# ButtonHack.net
KiCad netlist of a schematic drawn in EAGLE
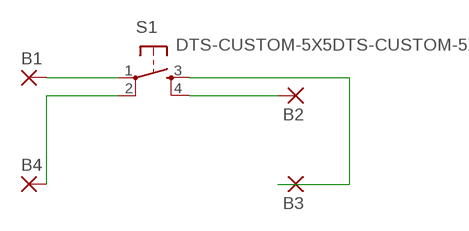
[diagram p0: schematic, sheet 1]

(export (version "E")
  (design (tool "Eeschema 10.0.6"))
  (components
    (comp (ref "B1")
      (value "2,54/0,8")
      (footprint "eagle-import:2,54_0,8")
      (libsource (lib "eagle-import") (part "2,54/0,8"))
    )
    (comp (ref "B2")
      (value "2,54/0,8")
      (footprint "eagle-import:2,54_0,8")
      (libsource (lib "eagle-import") (part "2,54/0,8"))
    )
    (comp (ref "B3")
      (value "2,54/0,8")
      (footprint "eagle-import:2,54_0,8")
      (libsource (lib "eagle-import") (part "2,54/0,8"))
    )
    (comp (ref "B4")
      (value "2,54/0,8")
      (footprint "eagle-import:2,54_0,8")
      (libsource (lib "eagle-import") (part "2,54/0,8"))
    )
    (comp (ref "S1")
      (value "DTS-CUSTOM-5X5DTS-CUSTOM-5X5")
      (footprint "eagle-import:DTS-CUSTOM-5X5")
      (libsource (lib "eagle-import") (part "DTS-CUSTOM-5X5DTS-CUSTOM-5X5"))
    )
  )
  (nets
    (net (code "1") (name "Net-(B1-P)") (class "Default")
      (node (ref "B1") (pin "1") (pinfunction "P_1") (pintype "passive"))
      (node (ref "S1") (pin "1") (pinfunction "1_1") (pintype "passive"))
    )
    (net (code "2") (name "Net-(B2-P)") (class "Default")
      (node (ref "B2") (pin "1") (pinfunction "P_1") (pintype "passive"))
      (node (ref "S1") (pin "4") (pinfunction "4_4") (pintype "passive"))
    )
    (net (code "3") (name "Net-(B3-P)") (class "Default")
      (node (ref "B3") (pin "1") (pinfunction "P_1") (pintype "passive"))
      (node (ref "S1") (pin "3") (pinfunction "3_3") (pintype "passive"))
    )
    (net (code "4") (name "Net-(B4-P)") (class "Default")
      (node (ref "B4") (pin "1") (pinfunction "P_1") (pintype "passive"))
      (node (ref "S1") (pin "2") (pinfunction "2_2") (pintype "passive"))
    )
  )
)
